# ProDoc_ChisFlash-MBC5-MAX-v1_22-R0603_32.net
KiCad netlist of a schematic drawn in EasyEDA Pro
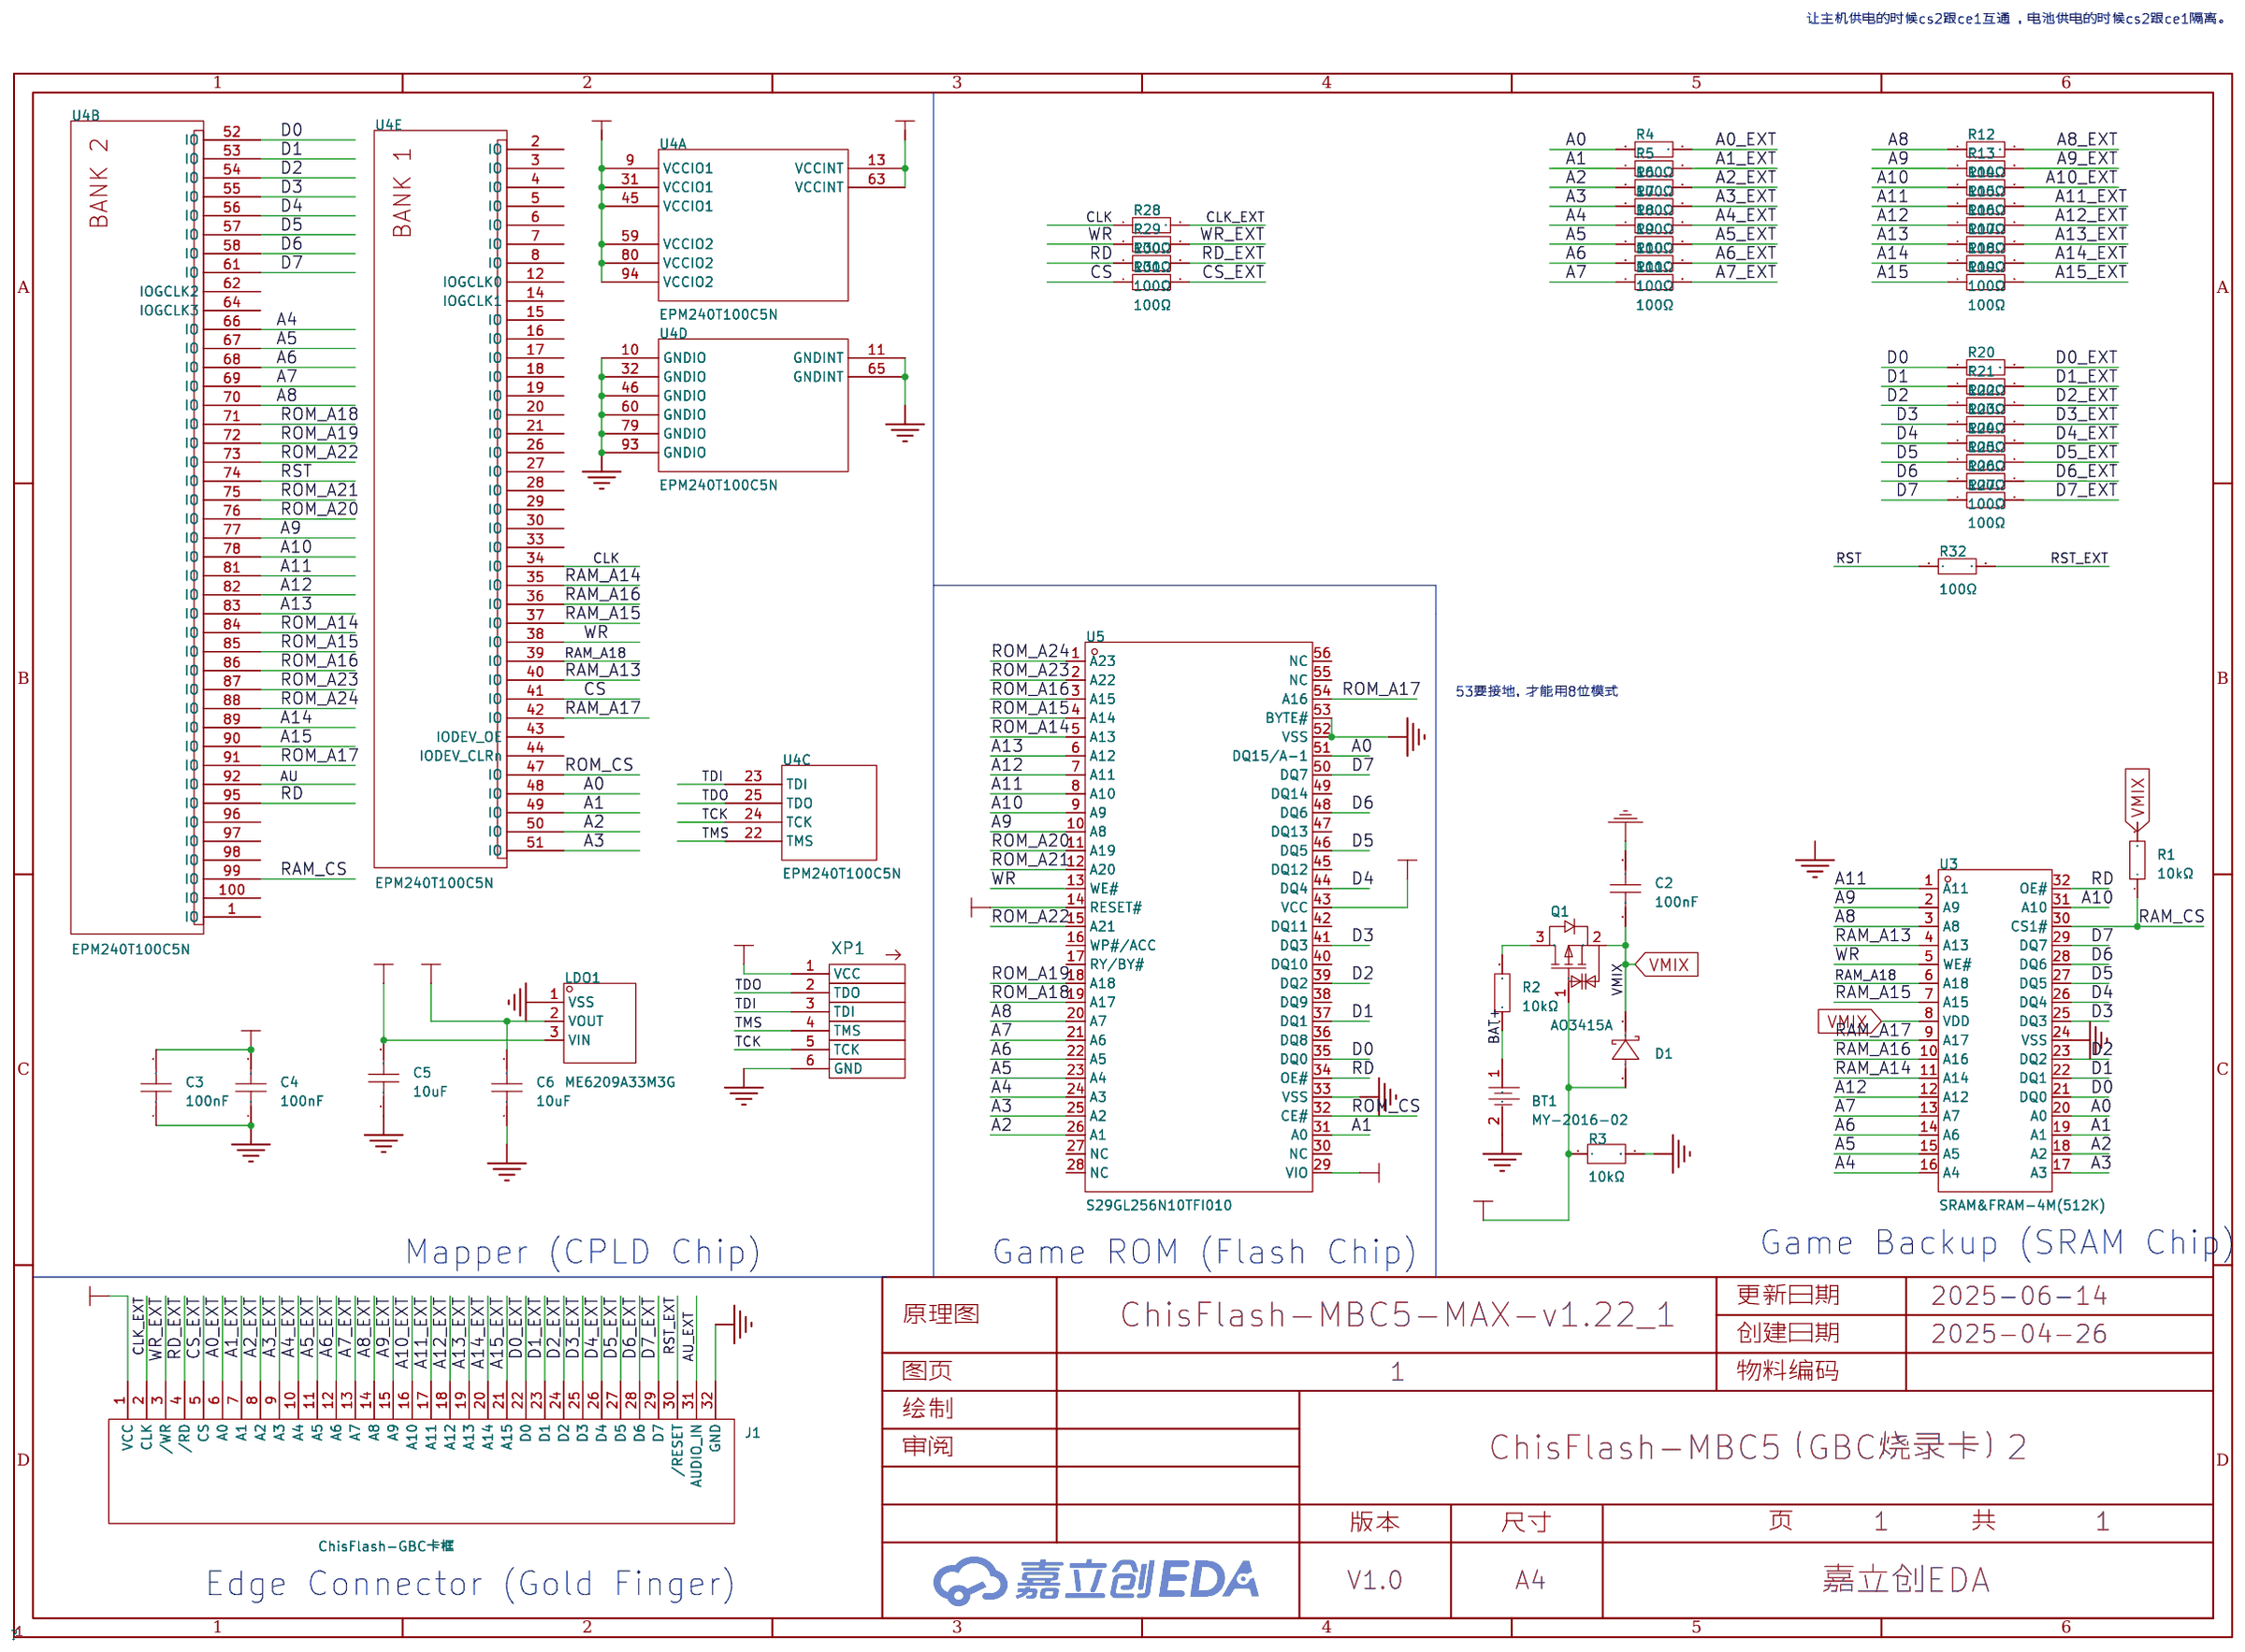
[diagram p0: schematic sheet]

(export (version "E")
  (design (tool "Eeschema 10.0.6"))
  (components
    (comp (ref "BT1")
      (value "MY-2016-02")
      (footprint "easyedapro:BAT-SMD_MY-2032-08")
      (description "连接器类型:电池扣;适用电池规格:CR2016;触头材质:磷青铜;触点电镀:镍;工作温度范围:-25°C~+85°C;")
      (fields (field (name "Manufacturer") "MYOUNG(美阳)"))
      (libsource (lib "easyedapro") (part "MY-2016-02"))
    )
    (comp (ref "C2")
      (value "100nF")
      (footprint "easyedapro:C0603")
      (description "容值:100nF;精度:±10%;额定电压:50V;材质(温度系数):X7R;")
      (fields
        (field (name "Manufacturer Part") "CGA0603X7R104K500JT")
        (field (name "Manufacturer") "HRE(芯声)")
      )
      (libsource (lib "easyedapro") (part "CGA0603X7R104K500JT"))
    )
    (comp (ref "C3")
      (value "100nF")
      (footprint "easyedapro:C0603")
      (description "容值:100nF;精度:±10%;额定电压:50V;材质(温度系数):X7R;")
      (fields
        (field (name "Manufacturer Part") "CGA0603X7R104K500JT")
        (field (name "Manufacturer") "HRE(芯声)")
      )
      (libsource (lib "easyedapro") (part "CGA0603X7R104K500JT"))
    )
    (comp (ref "C4")
      (value "100nF")
      (footprint "easyedapro:C0603")
      (description "容值:100nF;精度:±10%;额定电压:50V;材质(温度系数):X7R;")
      (fields
        (field (name "Manufacturer Part") "CGA0603X7R104K500JT")
        (field (name "Manufacturer") "HRE(芯声)")
      )
      (libsource (lib "easyedapro") (part "CGA0603X7R104K500JT"))
    )
    (comp (ref "C5")
      (value "10uF")
      (footprint "easyedapro:C0603")
      (description "容值:10uF;精度:±20%;额定电压:25V;材质(温度系数):X5R;")
      (fields
        (field (name "Manufacturer Part") "CL10A106MA8NRNC")
        (field (name "Manufacturer") "SAMSUNG(三星)")
      )
      (libsource (lib "easyedapro") (part "CL10A106MA8NRNC"))
    )
    (comp (ref "C6")
      (value "10uF")
      (footprint "easyedapro:C0603")
      (description "容值:10uF;精度:±20%;额定电压:25V;材质(温度系数):X5R;")
      (fields
        (field (name "Manufacturer Part") "CL10A106MA8NRNC")
        (field (name "Manufacturer") "SAMSUNG(三星)")
      )
      (libsource (lib "easyedapro") (part "CL10A106MA8NRNC"))
    )
    (comp (ref "D1")
      (value "RB751V-40")
      (footprint "easyedapro:SOD-323_L1.7-W1.3-LS2.6-RD-1")
      (description "二极管配置:独立式;正向压降(Vf):370mV@1mA;直流反向耐压(Vr):40V;平均整流电流(Io):30mA;")
      (fields (field (name "Manufacturer") "宏迦橙"))
      (libsource (lib "easyedapro") (part "RB751V-40_C7502691"))
    )
    (comp (ref "J1")
      (value "ChisFlash-GBC卡框")
      (footprint "easyedapro:ChisFlash-GBC卡框")
      (libsource (lib "easyedapro") (part "ChisFlash-GBC卡框"))
    )
    (comp (ref "LDO1")
      (value "ME6209A33M3G")
      (footprint "easyedapro:SOT-23-3_L2.9-W1.6-P1.90-LS2.8-BR")
      (description "输出类型:固定;最大输入电压:18V;输出电压:3.3V;最大输出电流:250mA;电源纹波抑制比(PSRR):-;输出极性:正极;")
      (fields (field (name "Manufacturer") "MICRONE(南京微盟)"))
      (libsource (lib "easyedapro") (part "ME6209A33M3G"))
    )
    (comp (ref "Q1")
      (value "AO3415A")
      (footprint "easyedapro:SOT-23-3_L3.0-W1.7-P0.95-LS2.9-BR")
      (fields (field (name "Manufacturer") "UMW(友台半导体)"))
      (libsource (lib "easyedapro") (part "AO3415A_C347479"))
    )
    (comp (ref "R1")
      (value "10kΩ")
      (footprint "easyedapro:R0603")
      (description "电阻类型:厚膜电阻;阻值:10kΩ;精度:±1%;功率:100mW;温度系数:±100ppm/°C;最大工作电压:75V;工作温度范围:-55°C~+155°C;")
      (fields
        (field (name "Manufacturer Part") "0603WAF1002T5E")
        (field (name "Manufacturer") "UNI-ROYAL(厚声)")
      )
      (libsource (lib "easyedapro") (part "0603WAF1002T5E"))
    )
    (comp (ref "R2")
      (value "10kΩ")
      (footprint "easyedapro:R0603")
      (description "电阻类型:厚膜电阻;阻值:10kΩ;精度:±1%;功率:100mW;温度系数:±100ppm/°C;最大工作电压:75V;工作温度范围:-55°C~+155°C;")
      (fields
        (field (name "Manufacturer Part") "0603WAF1002T5E")
        (field (name "Manufacturer") "UNI-ROYAL(厚声)")
      )
      (libsource (lib "easyedapro") (part "0603WAF1002T5E"))
    )
    (comp (ref "R3")
      (value "10kΩ")
      (footprint "easyedapro:R0603")
      (description "电阻类型:薄膜电阻;阻值:10kΩ;精度:±0.1%;功率:100mW;最大工作电压:75V;温度系数:±25ppm/°C;")
      (fields (field (name "Manufacturer Part") "RT0603BRD1010KL") (field (name "Manufacturer") "YAGEO(国巨)"))
      (libsource (lib "easyedapro") (part "RT0603BRD1010KL"))
    )
    (comp (ref "R4")
      (value "100Ω")
      (fields
        (field (name "Manufacturer Part") "0105WHJ0101TDE")
        (field (name "Manufacturer") "UNI-ROYAL(厚声)")
      )
      (libsource (lib "easyedapro") (part "0603WAF1000T5E"))
    )
    (comp (ref "R5")
      (value "100Ω")
      (fields
        (field (name "Manufacturer Part") "0105WHJ0101TDE")
        (field (name "Manufacturer") "UNI-ROYAL(厚声)")
      )
      (libsource (lib "easyedapro") (part "0603WAF1000T5E"))
    )
    (comp (ref "R6")
      (value "100Ω")
      (fields
        (field (name "Manufacturer Part") "0105WHJ0101TDE")
        (field (name "Manufacturer") "UNI-ROYAL(厚声)")
      )
      (libsource (lib "easyedapro") (part "0603WAF1000T5E"))
    )
    (comp (ref "R7")
      (value "100Ω")
      (fields
        (field (name "Manufacturer Part") "0105WHJ0101TDE")
        (field (name "Manufacturer") "UNI-ROYAL(厚声)")
      )
      (libsource (lib "easyedapro") (part "0603WAF1000T5E"))
    )
    (comp (ref "R8")
      (value "100Ω")
      (fields
        (field (name "Manufacturer Part") "0105WHJ0101TDE")
        (field (name "Manufacturer") "UNI-ROYAL(厚声)")
      )
      (libsource (lib "easyedapro") (part "0603WAF1000T5E"))
    )
    (comp (ref "R9")
      (value "100Ω")
      (fields
        (field (name "Manufacturer Part") "0105WHJ0101TDE")
        (field (name "Manufacturer") "UNI-ROYAL(厚声)")
      )
      (libsource (lib "easyedapro") (part "0603WAF1000T5E"))
    )
    (comp (ref "R10")
      (value "100Ω")
      (fields
        (field (name "Manufacturer Part") "0105WHJ0101TDE")
        (field (name "Manufacturer") "UNI-ROYAL(厚声)")
      )
      (libsource (lib "easyedapro") (part "0603WAF1000T5E"))
    )
    (comp (ref "R11")
      (value "100Ω")
      (fields
        (field (name "Manufacturer Part") "0105WHJ0101TDE")
        (field (name "Manufacturer") "UNI-ROYAL(厚声)")
      )
      (libsource (lib "easyedapro") (part "0603WAF1000T5E"))
    )
    (comp (ref "R12")
      (value "100Ω")
      (fields
        (field (name "Manufacturer Part") "0105WHJ0101TDE")
        (field (name "Manufacturer") "UNI-ROYAL(厚声)")
      )
      (libsource (lib "easyedapro") (part "0603WAF1000T5E"))
    )
    (comp (ref "R13")
      (value "100Ω")
      (fields
        (field (name "Manufacturer Part") "0105WHJ0101TDE")
        (field (name "Manufacturer") "UNI-ROYAL(厚声)")
      )
      (libsource (lib "easyedapro") (part "0603WAF1000T5E"))
    )
    (comp (ref "R14")
      (value "100Ω")
      (fields
        (field (name "Manufacturer Part") "0105WHJ0101TDE")
        (field (name "Manufacturer") "UNI-ROYAL(厚声)")
      )
      (libsource (lib "easyedapro") (part "0603WAF1000T5E"))
    )
    (comp (ref "R15")
      (value "100Ω")
      (fields
        (field (name "Manufacturer Part") "0105WHJ0101TDE")
        (field (name "Manufacturer") "UNI-ROYAL(厚声)")
      )
      (libsource (lib "easyedapro") (part "0603WAF1000T5E"))
    )
    (comp (ref "R16")
      (value "100Ω")
      (fields
        (field (name "Manufacturer Part") "0105WHJ0101TDE")
        (field (name "Manufacturer") "UNI-ROYAL(厚声)")
      )
      (libsource (lib "easyedapro") (part "0603WAF1000T5E"))
    )
    (comp (ref "R17")
      (value "100Ω")
      (fields
        (field (name "Manufacturer Part") "0105WHJ0101TDE")
        (field (name "Manufacturer") "UNI-ROYAL(厚声)")
      )
      (libsource (lib "easyedapro") (part "0603WAF1000T5E"))
    )
    (comp (ref "R18")
      (value "100Ω")
      (fields
        (field (name "Manufacturer Part") "0105WHJ0101TDE")
        (field (name "Manufacturer") "UNI-ROYAL(厚声)")
      )
      (libsource (lib "easyedapro") (part "0603WAF1000T5E"))
    )
    (comp (ref "R19")
      (value "100Ω")
      (fields
        (field (name "Manufacturer Part") "0105WHJ0101TDE")
        (field (name "Manufacturer") "UNI-ROYAL(厚声)")
      )
      (libsource (lib "easyedapro") (part "0603WAF1000T5E"))
    )
    (comp (ref "R20")
      (value "100Ω")
      (fields
        (field (name "Manufacturer Part") "0105WHJ0101TDE")
        (field (name "Manufacturer") "UNI-ROYAL(厚声)")
      )
      (libsource (lib "easyedapro") (part "0603WAF1000T5E"))
    )
    (comp (ref "R21")
      (value "100Ω")
      (fields
        (field (name "Manufacturer Part") "0105WHJ0101TDE")
        (field (name "Manufacturer") "UNI-ROYAL(厚声)")
      )
      (libsource (lib "easyedapro") (part "0603WAF1000T5E"))
    )
    (comp (ref "R22")
      (value "100Ω")
      (fields
        (field (name "Manufacturer Part") "0105WHJ0101TDE")
        (field (name "Manufacturer") "UNI-ROYAL(厚声)")
      )
      (libsource (lib "easyedapro") (part "0603WAF1000T5E"))
    )
    (comp (ref "R23")
      (value "100Ω")
      (fields
        (field (name "Manufacturer Part") "0105WHJ0101TDE")
        (field (name "Manufacturer") "UNI-ROYAL(厚声)")
      )
      (libsource (lib "easyedapro") (part "0603WAF1000T5E"))
    )
    (comp (ref "R24")
      (value "100Ω")
      (fields
        (field (name "Manufacturer Part") "0105WHJ0101TDE")
        (field (name "Manufacturer") "UNI-ROYAL(厚声)")
      )
      (libsource (lib "easyedapro") (part "0603WAF1000T5E"))
    )
    (comp (ref "R25")
      (value "100Ω")
      (fields
        (field (name "Manufacturer Part") "0105WHJ0101TDE")
        (field (name "Manufacturer") "UNI-ROYAL(厚声)")
      )
      (libsource (lib "easyedapro") (part "0603WAF1000T5E"))
    )
    (comp (ref "R26")
      (value "100Ω")
      (fields
        (field (name "Manufacturer Part") "0105WHJ0101TDE")
        (field (name "Manufacturer") "UNI-ROYAL(厚声)")
      )
      (libsource (lib "easyedapro") (part "0603WAF1000T5E"))
    )
    (comp (ref "R27")
      (value "100Ω")
      (fields
        (field (name "Manufacturer Part") "0105WHJ0101TDE")
        (field (name "Manufacturer") "UNI-ROYAL(厚声)")
      )
      (libsource (lib "easyedapro") (part "0603WAF1000T5E"))
    )
    (comp (ref "R28")
      (value "100Ω")
      (fields
        (field (name "Manufacturer Part") "0105WHJ0101TDE")
        (field (name "Manufacturer") "UNI-ROYAL(厚声)")
      )
      (libsource (lib "easyedapro") (part "0603WAF1000T5E"))
    )
    (comp (ref "R29")
      (value "100Ω")
      (fields
        (field (name "Manufacturer Part") "0105WHJ0101TDE")
        (field (name "Manufacturer") "UNI-ROYAL(厚声)")
      )
      (libsource (lib "easyedapro") (part "0603WAF1000T5E"))
    )
    (comp (ref "R30")
      (value "100Ω")
      (fields
        (field (name "Manufacturer Part") "0105WHJ0101TDE")
        (field (name "Manufacturer") "UNI-ROYAL(厚声)")
      )
      (libsource (lib "easyedapro") (part "0603WAF1000T5E"))
    )
    (comp (ref "R31")
      (value "100Ω")
      (fields
        (field (name "Manufacturer Part") "0105WHJ0101TDE")
        (field (name "Manufacturer") "UNI-ROYAL(厚声)")
      )
      (libsource (lib "easyedapro") (part "0603WAF1000T5E"))
    )
    (comp (ref "R32")
      (value "100Ω")
      (fields
        (field (name "Manufacturer Part") "0105WHJ0101TDE")
        (field (name "Manufacturer") "UNI-ROYAL(厚声)")
      )
      (libsource (lib "easyedapro") (part "0603WAF1000T5E"))
    )
    (comp (ref "U3")
      (value "SRAM&FRAM-4M(512K)")
      (footprint "easyedapro:TSSOP-TSOP二合一_1")
      (libsource (lib "easyedapro") (part "SRAM&FRAM-4M(512K)"))
    )
    (comp (ref "U4")
      (value "EPM240T100C5N")
      (footprint "easyedapro:TQFP-100_L14.0-W14.0-P0.50-LS16.0-BL")
      (description "类型:其它PLD;逻辑门数量:-;逻辑单元数:-;逻辑阵列块数:240;")
      (fields (field (name "Manufacturer") "Intel/Altera"))
      (libsource (lib "easyedapro") (part "EPM240T100C5N"))
    )
    (comp (ref "U5")
      (value "S29GL256N10TFI010")
      (footprint "easyedapro:TSOP-56_L18.4-W14.0-P0.50-LS20.0-TL")
      (libsource (lib "easyedapro") (part "S29GL256N10TFI010"))
    )
    (comp (ref "XP1")
      (value "JTAG")
      (footprint "easyedapro:HDR-TH_6P-P1.27-V-M-1")
      (libsource (lib "easyedapro") (part "jtag"))
    )
  )
  (nets
    (net (code "1") (name "+3V3") (class "Default")
      (node (ref "C3") (pin "2") (pinfunction "2_2") (pintype "unspecified"))
      (node (ref "C4") (pin "2") (pinfunction "2_2") (pintype "unspecified"))
      (node (ref "C6") (pin "2") (pinfunction "2_2") (pintype "unspecified"))
      (node (ref "D1") (pin "2") (pinfunction "A_2") (pintype "unspecified"))
      (node (ref "LDO1") (pin "2") (pinfunction "VOUT_2") (pintype "unspecified"))
      (node (ref "Q1") (pin "1") (pinfunction "G_1") (pintype "unspecified"))
      (node (ref "R3") (pin "1") (pinfunction "1_1") (pintype "unspecified"))
      (node (ref "U4") (pin "13") (pinfunction "VCCINT_13") (pintype "unspecified"))
      (node (ref "U4") (pin "31") (pinfunction "VCCIO1_31") (pintype "unspecified"))
      (node (ref "U4") (pin "45") (pinfunction "VCCIO1_45") (pintype "unspecified"))
      (node (ref "U4") (pin "59") (pinfunction "VCCIO2_59") (pintype "unspecified"))
      (node (ref "U4") (pin "63") (pinfunction "VCCINT_63") (pintype "unspecified"))
      (node (ref "U4") (pin "80") (pinfunction "VCCIO2_80") (pintype "unspecified"))
      (node (ref "U4") (pin "9") (pinfunction "VCCIO1_9") (pintype "unspecified"))
      (node (ref "U4") (pin "94") (pinfunction "VCCIO2_94") (pintype "unspecified"))
      (node (ref "U5") (pin "14") (pinfunction "RESET#_14") (pintype "unspecified"))
      (node (ref "U5") (pin "29") (pinfunction "VIO_29") (pintype "unspecified"))
      (node (ref "U5") (pin "43") (pinfunction "VCC_43") (pintype "unspecified"))
      (node (ref "XP1") (pin "1") (pinfunction "VCC_1") (pintype "output"))
    )
    (net (code "2") (name "+5V") (class "Default")
      (node (ref "C5") (pin "2") (pinfunction "2_2") (pintype "unspecified"))
      (node (ref "J1") (pin "1") (pinfunction "VCC_1") (pintype "unspecified"))
      (node (ref "LDO1") (pin "3") (pinfunction "VIN_3") (pintype "unspecified"))
    )
    (net (code "3") (name "/A0") (class "Default")
      (node (ref "R4") (pin "1") (pinfunction "1_1") (pintype "input"))
      (node (ref "U3") (pin "20") (pinfunction "A0_20") (pintype "unspecified"))
      (node (ref "U4") (pin "48") (pinfunction "IO_48") (pintype "bidirectional"))
      (node (ref "U5") (pin "51") (pinfunction "DQ15/A-1_51") (pintype "unspecified"))
    )
    (net (code "4") (name "/A0_EXT") (class "Default")
      (node (ref "J1") (pin "6") (pinfunction "A0_6") (pintype "unspecified"))
      (node (ref "R4") (pin "2") (pinfunction "2_2") (pintype "input"))
    )
    (net (code "5") (name "/A1") (class "Default")
      (node (ref "R5") (pin "1") (pinfunction "1_1") (pintype "input"))
      (node (ref "U3") (pin "19") (pinfunction "A1_19") (pintype "unspecified"))
      (node (ref "U4") (pin "49") (pinfunction "IO_49") (pintype "bidirectional"))
      (node (ref "U5") (pin "31") (pinfunction "A0_31") (pintype "unspecified"))
    )
    (net (code "6") (name "/A1_EXT") (class "Default")
      (node (ref "J1") (pin "7") (pinfunction "A1_7") (pintype "unspecified"))
      (node (ref "R5") (pin "2") (pinfunction "2_2") (pintype "input"))
    )
    (net (code "7") (name "/A2") (class "Default")
      (node (ref "R6") (pin "1") (pinfunction "1_1") (pintype "input"))
      (node (ref "U3") (pin "18") (pinfunction "A2_18") (pintype "unspecified"))
      (node (ref "U4") (pin "50") (pinfunction "IO_50") (pintype "bidirectional"))
      (node (ref "U5") (pin "26") (pinfunction "A1_26") (pintype "unspecified"))
    )
    (net (code "8") (name "/A2_EXT") (class "Default")
      (node (ref "J1") (pin "8") (pinfunction "A2_8") (pintype "unspecified"))
      (node (ref "R6") (pin "2") (pinfunction "2_2") (pintype "input"))
    )
    (net (code "9") (name "/A3") (class "Default")
      (node (ref "R7") (pin "1") (pinfunction "1_1") (pintype "input"))
      (node (ref "U3") (pin "17") (pinfunction "A3_17") (pintype "unspecified"))
      (node (ref "U4") (pin "51") (pinfunction "IO_51") (pintype "bidirectional"))
      (node (ref "U5") (pin "25") (pinfunction "A2_25") (pintype "unspecified"))
    )
    (net (code "10") (name "/A3_EXT") (class "Default")
      (node (ref "J1") (pin "9") (pinfunction "A3_9") (pintype "unspecified"))
      (node (ref "R7") (pin "2") (pinfunction "2_2") (pintype "input"))
    )
    (net (code "11") (name "/A4") (class "Default")
      (node (ref "R8") (pin "1") (pinfunction "1_1") (pintype "input"))
      (node (ref "U3") (pin "16") (pinfunction "A4_16") (pintype "unspecified"))
      (node (ref "U4") (pin "66") (pinfunction "IO_66") (pintype "bidirectional"))
      (node (ref "U5") (pin "24") (pinfunction "A3_24") (pintype "unspecified"))
    )
    (net (code "12") (name "/A4_EXT") (class "Default")
      (node (ref "J1") (pin "10") (pinfunction "A4_10") (pintype "unspecified"))
      (node (ref "R8") (pin "2") (pinfunction "2_2") (pintype "input"))
    )
    (net (code "13") (name "/A5") (class "Default")
      (node (ref "R9") (pin "1") (pinfunction "1_1") (pintype "input"))
      (node (ref "U3") (pin "15") (pinfunction "A5_15") (pintype "unspecified"))
      (node (ref "U4") (pin "67") (pinfunction "IO_67") (pintype "bidirectional"))
      (node (ref "U5") (pin "23") (pinfunction "A4_23") (pintype "unspecified"))
    )
    (net (code "14") (name "/A5_EXT") (class "Default")
      (node (ref "J1") (pin "11") (pinfunction "A5_11") (pintype "unspecified"))
      (node (ref "R9") (pin "2") (pinfunction "2_2") (pintype "input"))
    )
    (net (code "15") (name "/A6") (class "Default")
      (node (ref "R10") (pin "1") (pinfunction "1_1") (pintype "input"))
      (node (ref "U3") (pin "14") (pinfunction "A6_14") (pintype "unspecified"))
      (node (ref "U4") (pin "68") (pinfunction "IO_68") (pintype "bidirectional"))
      (node (ref "U5") (pin "22") (pinfunction "A5_22") (pintype "unspecified"))
    )
    (net (code "16") (name "/A6_EXT") (class "Default")
      (node (ref "J1") (pin "12") (pinfunction "A6_12") (pintype "unspecified"))
      (node (ref "R10") (pin "2") (pinfunction "2_2") (pintype "input"))
    )
    (net (code "17") (name "/A7") (class "Default")
      (node (ref "R11") (pin "1") (pinfunction "1_1") (pintype "input"))
      (node (ref "U3") (pin "13") (pinfunction "A7_13") (pintype "unspecified"))
      (node (ref "U4") (pin "69") (pinfunction "IO_69") (pintype "bidirectional"))
      (node (ref "U5") (pin "21") (pinfunction "A6_21") (pintype "unspecified"))
    )
    (net (code "18") (name "/A7_EXT") (class "Default")
      (node (ref "J1") (pin "13") (pinfunction "A7_13") (pintype "unspecified"))
      (node (ref "R11") (pin "2") (pinfunction "2_2") (pintype "input"))
    )
    (net (code "19") (name "/A8") (class "Default")
      (node (ref "R12") (pin "1") (pinfunction "1_1") (pintype "input"))
      (node (ref "U3") (pin "3") (pinfunction "A8_3") (pintype "unspecified"))
      (node (ref "U4") (pin "70") (pinfunction "IO_70") (pintype "bidirectional"))
      (node (ref "U5") (pin "20") (pinfunction "A7_20") (pintype "unspecified"))
    )
    (net (code "20") (name "/A8_EXT") (class "Default")
      (node (ref "J1") (pin "14") (pinfunction "A8_14") (pintype "unspecified"))
      (node (ref "R12") (pin "2") (pinfunction "2_2") (pintype "input"))
    )
    (net (code "21") (name "/A9") (class "Default")
      (node (ref "R13") (pin "1") (pinfunction "1_1") (pintype "input"))
      (node (ref "U3") (pin "2") (pinfunction "A9_2") (pintype "unspecified"))
      (node (ref "U4") (pin "77") (pinfunction "IO_77") (pintype "bidirectional"))
      (node (ref "U5") (pin "10") (pinfunction "A8_10") (pintype "unspecified"))
    )
    (net (code "22") (name "/A9_EXT") (class "Default")
      (node (ref "J1") (pin "15") (pinfunction "A9_15") (pintype "unspecified"))
      (node (ref "R13") (pin "2") (pinfunction "2_2") (pintype "input"))
    )
    (net (code "23") (name "/A10") (class "Default")
      (node (ref "R14") (pin "1") (pinfunction "1_1") (pintype "input"))
      (node (ref "U3") (pin "31") (pinfunction "A10_31") (pintype "unspecified"))
      (node (ref "U4") (pin "78") (pinfunction "IO_78") (pintype "bidirectional"))
      (node (ref "U5") (pin "9") (pinfunction "A9_9") (pintype "unspecified"))
    )
    (net (code "24") (name "/A10_EXT") (class "Default")
      (node (ref "J1") (pin "16") (pinfunction "A10_16") (pintype "unspecified"))
      (node (ref "R14") (pin "2") (pinfunction "2_2") (pintype "input"))
    )
    (net (code "25") (name "/A11") (class "Default")
      (node (ref "R15") (pin "1") (pinfunction "1_1") (pintype "input"))
      (node (ref "U3") (pin "1") (pinfunction "A11_1") (pintype "unspecified"))
      (node (ref "U4") (pin "81") (pinfunction "IO_81") (pintype "bidirectional"))
      (node (ref "U5") (pin "8") (pinfunction "A10_8") (pintype "unspecified"))
    )
    (net (code "26") (name "/A11_EXT") (class "Default")
      (node (ref "J1") (pin "17") (pinfunction "A11_17") (pintype "unspecified"))
      (node (ref "R15") (pin "2") (pinfunction "2_2") (pintype "input"))
    )
    (net (code "27") (name "/A12") (class "Default")
      (node (ref "R16") (pin "1") (pinfunction "1_1") (pintype "input"))
      (node (ref "U3") (pin "12") (pinfunction "A12_12") (pintype "unspecified"))
      (node (ref "U4") (pin "82") (pinfunction "IO_82") (pintype "bidirectional"))
      (node (ref "U5") (pin "7") (pinfunction "A11_7") (pintype "unspecified"))
    )
    (net (code "28") (name "/A12_EXT") (class "Default")
      (node (ref "J1") (pin "18") (pinfunction "A12_18") (pintype "unspecified"))
      (node (ref "R16") (pin "2") (pinfunction "2_2") (pintype "input"))
    )
    (net (code "29") (name "/A13") (class "Default")
      (node (ref "R17") (pin "1") (pinfunction "1_1") (pintype "input"))
      (node (ref "U4") (pin "83") (pinfunction "IO_83") (pintype "bidirectional"))
      (node (ref "U5") (pin "6") (pinfunction "A12_6") (pintype "unspecified"))
    )
    (net (code "30") (name "/A13_EXT") (class "Default")
      (node (ref "J1") (pin "19") (pinfunction "A13_19") (pintype "unspecified"))
      (node (ref "R17") (pin "2") (pinfunction "2_2") (pintype "input"))
    )
    (net (code "31") (name "/A14") (class "Default")
      (node (ref "R18") (pin "1") (pinfunction "1_1") (pintype "input"))
      (node (ref "U4") (pin "89") (pinfunction "IO_89") (pintype "bidirectional"))
    )
    (net (code "32") (name "/A14_EXT") (class "Default")
      (node (ref "J1") (pin "20") (pinfunction "A14_20") (pintype "unspecified"))
      (node (ref "R18") (pin "2") (pinfunction "2_2") (pintype "input"))
    )
    (net (code "33") (name "/A15") (class "Default")
      (node (ref "R19") (pin "1") (pinfunction "1_1") (pintype "input"))
      (node (ref "U4") (pin "90") (pinfunction "IO_90") (pintype "bidirectional"))
    )
    (net (code "34") (name "/A15_EXT") (class "Default")
      (node (ref "J1") (pin "21") (pinfunction "A15_21") (pintype "unspecified"))
      (node (ref "R19") (pin "2") (pinfunction "2_2") (pintype "input"))
    )
    (net (code "35") (name "/AU") (class "Default")
      (node (ref "U4") (pin "92") (pinfunction "IO_92") (pintype "bidirectional"))
    )
    (net (code "36") (name "/AU_EXT") (class "Default")
      (node (ref "J1") (pin "31") (pinfunction "AUDIO_IN_31") (pintype "unspecified"))
    )
    (net (code "37") (name "/BAT+") (class "Default")
      (node (ref "BT1") (pin "1") (pinfunction "1_1") (pintype "input"))
      (node (ref "R2") (pin "1") (pinfunction "1_1") (pintype "input"))
    )
    (net (code "38") (name "/CLK") (class "Default")
      (node (ref "R28") (pin "1") (pinfunction "1_1") (pintype "input"))
      (node (ref "U4") (pin "34") (pinfunction "IO_34") (pintype "bidirectional"))
    )
    (net (code "39") (name "/CLK_EXT") (class "Default")
      (node (ref "J1") (pin "2") (pinfunction "CLK_2") (pintype "unspecified"))
      (node (ref "R28") (pin "2") (pinfunction "2_2") (pintype "input"))
    )
    (net (code "40") (name "/CS") (class "Default")
      (node (ref "R31") (pin "1") (pinfunction "1_1") (pintype "input"))
      (node (ref "U4") (pin "41") (pinfunction "IO_41") (pintype "bidirectional"))
    )
    (net (code "41") (name "/CS_EXT") (class "Default")
      (node (ref "J1") (pin "5") (pinfunction "CS_5") (pintype "unspecified"))
      (node (ref "R31") (pin "2") (pinfunction "2_2") (pintype "input"))
    )
    (net (code "42") (name "/D0") (class "Default")
      (node (ref "R20") (pin "1") (pinfunction "1_1") (pintype "input"))
      (node (ref "U3") (pin "21") (pinfunction "DQ0_21") (pintype "unspecified"))
      (node (ref "U4") (pin "52") (pinfunction "IO_52") (pintype "bidirectional"))
      (node (ref "U5") (pin "35") (pinfunction "DQ0_35") (pintype "unspecified"))
    )
    (net (code "43") (name "/D0_EXT") (class "Default")
      (node (ref "J1") (pin "22") (pinfunction "D0_22") (pintype "unspecified"))
      (node (ref "R20") (pin "2") (pinfunction "2_2") (pintype "input"))
    )
    (net (code "44") (name "/D1") (class "Default")
      (node (ref "R21") (pin "1") (pinfunction "1_1") (pintype "input"))
      (node (ref "U3") (pin "22") (pinfunction "DQ1_22") (pintype "unspecified"))
      (node (ref "U4") (pin "53") (pinfunction "IO_53") (pintype "bidirectional"))
      (node (ref "U5") (pin "37") (pinfunction "DQ1_37") (pintype "unspecified"))
    )
    (net (code "45") (name "/D1_EXT") (class "Default")
      (node (ref "J1") (pin "23") (pinfunction "D1_23") (pintype "unspecified"))
      (node (ref "R21") (pin "2") (pinfunction "2_2") (pintype "input"))
    )
    (net (code "46") (name "/D2") (class "Default")
      (node (ref "R22") (pin "1") (pinfunction "1_1") (pintype "input"))
      (node (ref "U3") (pin "23") (pinfunction "DQ2_23") (pintype "unspecified"))
      (node (ref "U4") (pin "54") (pinfunction "IO_54") (pintype "bidirectional"))
      (node (ref "U5") (pin "39") (pinfunction "DQ2_39") (pintype "unspecified"))
    )
    (net (code "47") (name "/D2_EXT") (class "Default")
      (node (ref "J1") (pin "24") (pinfunction "D2_24") (pintype "unspecified"))
      (node (ref "R22") (pin "2") (pinfunction "2_2") (pintype "input"))
    )
    (net (code "48") (name "/D3") (class "Default")
      (node (ref "R23") (pin "1") (pinfunction "1_1") (pintype "input"))
      (node (ref "U3") (pin "25") (pinfunction "DQ3_25") (pintype "unspecified"))
      (node (ref "U4") (pin "55") (pinfunction "IO_55") (pintype "bidirectional"))
      (node (ref "U5") (pin "41") (pinfunction "DQ3_41") (pintype "unspecified"))
    )
    (net (code "49") (name "/D3_EXT") (class "Default")
      (node (ref "J1") (pin "25") (pinfunction "D3_25") (pintype "unspecified"))
      (node (ref "R23") (pin "2") (pinfunction "2_2") (pintype "input"))
    )
    (net (code "50") (name "/D4") (class "Default")
      (node (ref "R24") (pin "1") (pinfunction "1_1") (pintype "input"))
      (node (ref "U3") (pin "26") (pinfunction "DQ4_26") (pintype "unspecified"))
      (node (ref "U4") (pin "56") (pinfunction "IO_56") (pintype "bidirectional"))
      (node (ref "U5") (pin "44") (pinfunction "DQ4_44") (pintype "unspecified"))
    )
    (net (code "51") (name "/D4_EXT") (class "Default")
      (node (ref "J1") (pin "26") (pinfunction "D4_26") (pintype "unspecified"))
      (node (ref "R24") (pin "2") (pinfunction "2_2") (pintype "input"))
    )
    (net (code "52") (name "/D5") (class "Default")
      (node (ref "R25") (pin "1") (pinfunction "1_1") (pintype "input"))
      (node (ref "U3") (pin "27") (pinfunction "DQ5_27") (pintype "unspecified"))
      (node (ref "U4") (pin "57") (pinfunction "IO_57") (pintype "bidirectional"))
      (node (ref "U5") (pin "46") (pinfunction "DQ5_46") (pintype "unspecified"))
    )
    (net (code "53") (name "/D5_EXT") (class "Default")
      (node (ref "J1") (pin "27") (pinfunction "D5_27") (pintype "unspecified"))
      (node (ref "R25") (pin "2") (pinfunction "2_2") (pintype "input"))
    )
    (net (code "54") (name "/D6") (class "Default")
      (node (ref "R26") (pin "1") (pinfunction "1_1") (pintype "input"))
      (node (ref "U3") (pin "28") (pinfunction "DQ6_28") (pintype "unspecified"))
      (node (ref "U4") (pin "58") (pinfunction "IO_58") (pintype "bidirectional"))
      (node (ref "U5") (pin "48") (pinfunction "DQ6_48") (pintype "unspecified"))
    )
    (net (code "55") (name "/D6_EXT") (class "Default")
      (node (ref "J1") (pin "28") (pinfunction "D6_28") (pintype "unspecified"))
      (node (ref "R26") (pin "2") (pinfunction "2_2") (pintype "input"))
    )
    (net (code "56") (name "/D7") (class "Default")
      (node (ref "R27") (pin "1") (pinfunction "1_1") (pintype "input"))
      (node (ref "U3") (pin "29") (pinfunction "DQ7_29") (pintype "unspecified"))
      (node (ref "U4") (pin "61") (pinfunction "IO_61") (pintype "bidirectional"))
      (node (ref "U5") (pin "50") (pinfunction "DQ7_50") (pintype "unspecified"))
    )
    (net (code "57") (name "/D7_EXT") (class "Default")
      (node (ref "J1") (pin "29") (pinfunction "D7_29") (pintype "unspecified"))
      (node (ref "R27") (pin "2") (pinfunction "2_2") (pintype "input"))
    )
    (net (code "58") (name "/RAM_A13") (class "Default")
      (node (ref "U3") (pin "4") (pinfunction "A13_4") (pintype "unspecified"))
      (node (ref "U4") (pin "40") (pinfunction "IO_40") (pintype "bidirectional"))
    )
    (net (code "59") (name "/RAM_A14") (class "Default")
      (node (ref "U3") (pin "11") (pinfunction "A14_11") (pintype "unspecified"))
      (node (ref "U4") (pin "35") (pinfunction "IO_35") (pintype "bidirectional"))
    )
    (net (code "60") (name "/RAM_A15") (class "Default")
      (node (ref "U3") (pin "7") (pinfunction "A15_7") (pintype "unspecified"))
      (node (ref "U4") (pin "37") (pinfunction "IO_37") (pintype "bidirectional"))
    )
    (net (code "61") (name "/RAM_A16") (class "Default")
      (node (ref "U3") (pin "10") (pinfunction "A16_10") (pintype "unspecified"))
      (node (ref "U4") (pin "36") (pinfunction "IO_36") (pintype "bidirectional"))
    )
    (net (code "62") (name "/RAM_A17") (class "Default")
      (node (ref "U3") (pin "9") (pinfunction "A17_9") (pintype "unspecified"))
      (node (ref "U4") (pin "42") (pinfunction "IO_42") (pintype "bidirectional"))
    )
    (net (code "63") (name "/RAM_A18") (class "Default")
      (node (ref "U3") (pin "6") (pinfunction "A18_6") (pintype "unspecified"))
      (node (ref "U4") (pin "39") (pinfunction "IO_39") (pintype "bidirectional"))
    )
    (net (code "64") (name "/RAM_CS") (class "Default")
      (node (ref "R1") (pin "1") (pinfunction "1_1") (pintype "input"))
      (node (ref "U3") (pin "30") (pinfunction "CS1#_30") (pintype "unspecified"))
      (node (ref "U4") (pin "99") (pinfunction "IO_99") (pintype "bidirectional"))
    )
    (net (code "65") (name "/RD") (class "Default")
      (node (ref "R30") (pin "1") (pinfunction "1_1") (pintype "input"))
      (node (ref "U3") (pin "32") (pinfunction "OE#_32") (pintype "unspecified"))
      (node (ref "U4") (pin "95") (pinfunction "IO_95") (pintype "bidirectional"))
      (node (ref "U5") (pin "34") (pinfunction "OE#_34") (pintype "unspecified"))
    )
    (net (code "66") (name "/RD_EXT") (class "Default")
      (node (ref "J1") (pin "4") (pinfunction "/RD_4") (pintype "unspecified"))
      (node (ref "R30") (pin "2") (pinfunction "2_2") (pintype "input"))
    )
    (net (code "67") (name "/ROM_A14") (class "Default")
      (node (ref "U4") (pin "84") (pinfunction "IO_84") (pintype "bidirectional"))
      (node (ref "U5") (pin "5") (pinfunction "A13_5") (pintype "unspecified"))
    )
    (net (code "68") (name "/ROM_A15") (class "Default")
      (node (ref "U4") (pin "85") (pinfunction "IO_85") (pintype "bidirectional"))
      (node (ref "U5") (pin "4") (pinfunction "A14_4") (pintype "unspecified"))
    )
    (net (code "69") (name "/ROM_A16") (class "Default")
      (node (ref "U4") (pin "86") (pinfunction "IO_86") (pintype "bidirectional"))
      (node (ref "U5") (pin "3") (pinfunction "A15_3") (pintype "unspecified"))
    )
    (net (code "70") (name "/ROM_A17") (class "Default")
      (node (ref "U4") (pin "91") (pinfunction "IO_91") (pintype "bidirectional"))
      (node (ref "U5") (pin "54") (pinfunction "A16_54") (pintype "unspecified"))
    )
    (net (code "71") (name "/ROM_A18") (class "Default")
      (node (ref "U4") (pin "71") (pinfunction "IO_71") (pintype "bidirectional"))
      (node (ref "U5") (pin "19") (pinfunction "A17_19") (pintype "unspecified"))
    )
    (net (code "72") (name "/ROM_A19") (class "Default")
      (node (ref "U4") (pin "72") (pinfunction "IO_72") (pintype "bidirectional"))
      (node (ref "U5") (pin "18") (pinfunction "A18_18") (pintype "unspecified"))
    )
    (net (code "73") (name "/ROM_A20") (class "Default")
      (node (ref "U4") (pin "76") (pinfunction "IO_76") (pintype "bidirectional"))
      (node (ref "U5") (pin "11") (pinfunction "A19_11") (pintype "unspecified"))
    )
    (net (code "74") (name "/ROM_A21") (class "Default")
      (node (ref "U4") (pin "75") (pinfunction "IO_75") (pintype "bidirectional"))
      (node (ref "U5") (pin "12") (pinfunction "A20_12") (pintype "unspecified"))
    )
    (net (code "75") (name "/ROM_A22") (class "Default")
      (node (ref "U4") (pin "73") (pinfunction "IO_73") (pintype "bidirectional"))
      (node (ref "U5") (pin "15") (pinfunction "A21_15") (pintype "unspecified"))
    )
    (net (code "76") (name "/ROM_A23") (class "Default")
      (node (ref "U4") (pin "87") (pinfunction "IO_87") (pintype "bidirectional"))
      (node (ref "U5") (pin "2") (pinfunction "A22_2") (pintype "unspecified"))
    )
    (net (code "77") (name "/ROM_A24") (class "Default")
      (node (ref "U4") (pin "88") (pinfunction "IO_88") (pintype "bidirectional"))
      (node (ref "U5") (pin "1") (pinfunction "A23_1") (pintype "unspecified"))
    )
    (net (code "78") (name "/ROM_CS") (class "Default")
      (node (ref "U4") (pin "47") (pinfunction "IO_47") (pintype "bidirectional"))
      (node (ref "U5") (pin "32") (pinfunction "CE#_32") (pintype "unspecified"))
    )
    (net (code "79") (name "/RST") (class "Default")
      (node (ref "R32") (pin "1") (pinfunction "1_1") (pintype "input"))
      (node (ref "U4") (pin "74") (pinfunction "IO_74") (pintype "bidirectional"))
    )
    (net (code "80") (name "/RST_EXT") (class "Default")
      (node (ref "J1") (pin "30") (pinfunction "/RESET_30") (pintype "unspecified"))
      (node (ref "R32") (pin "2") (pinfunction "2_2") (pintype "input"))
    )
    (net (code "81") (name "/TCK") (class "Default")
      (node (ref "U4") (pin "24") (pinfunction "TCK_24") (pintype "unspecified"))
      (node (ref "XP1") (pin "5") (pinfunction "TCK_5") (pintype "input"))
    )
    (net (code "82") (name "/TDI") (class "Default")
      (node (ref "U4") (pin "23") (pinfunction "TDI_23") (pintype "unspecified"))
      (node (ref "XP1") (pin "3") (pinfunction "TDI_3") (pintype "output"))
    )
    (net (code "83") (name "/TDO") (class "Default")
      (node (ref "U4") (pin "25") (pinfunction "TDO_25") (pintype "output"))
      (node (ref "XP1") (pin "2") (pinfunction "TDO_2") (pintype "output"))
    )
    (net (code "84") (name "/TMS") (class "Default")
      (node (ref "U4") (pin "22") (pinfunction "TMS_22") (pintype "unspecified"))
      (node (ref "XP1") (pin "4") (pinfunction "TMS_4") (pintype "output"))
    )
    (net (code "85") (name "/WR") (class "Default")
      (node (ref "R29") (pin "1") (pinfunction "1_1") (pintype "input"))
      (node (ref "U3") (pin "5") (pinfunction "WE#_5") (pintype "unspecified"))
      (node (ref "U4") (pin "38") (pinfunction "IO_38") (pintype "bidirectional"))
      (node (ref "U5") (pin "13") (pinfunction "WE#_13") (pintype "unspecified"))
    )
    (net (code "86") (name "/WR_EXT") (class "Default")
      (node (ref "J1") (pin "3") (pinfunction "/WR_3") (pintype "unspecified"))
      (node (ref "R29") (pin "2") (pinfunction "2_2") (pintype "input"))
    )
    (net (code "87") (name "GND") (class "Default")
      (node (ref "BT1") (pin "2") (pinfunction "2_2") (pintype "input"))
      (node (ref "C2") (pin "1") (pinfunction "1_1") (pintype "unspecified"))
      (node (ref "C3") (pin "1") (pinfunction "1_1") (pintype "unspecified"))
      (node (ref "C4") (pin "1") (pinfunction "1_1") (pintype "unspecified"))
      (node (ref "C5") (pin "1") (pinfunction "1_1") (pintype "unspecified"))
      (node (ref "C6") (pin "1") (pinfunction "1_1") (pintype "unspecified"))
      (node (ref "J1") (pin "32") (pinfunction "GND_32") (pintype "unspecified"))
      (node (ref "LDO1") (pin "1") (pinfunction "VSS_1") (pintype "unspecified"))
      (node (ref "R3") (pin "2") (pinfunction "2_2") (pintype "unspecified"))
      (node (ref "U3") (pin "24") (pinfunction "VSS_24") (pintype "unspecified"))
      (node (ref "U4") (pin "10") (pinfunction "GNDIO_10") (pintype "unspecified"))
      (node (ref "U4") (pin "11") (pinfunction "GNDINT_11") (pintype "unspecified"))
      (node (ref "U4") (pin "32") (pinfunction "GNDIO_32") (pintype "unspecified"))
      (node (ref "U4") (pin "46") (pinfunction "GNDIO_46") (pintype "unspecified"))
      (node (ref "U4") (pin "60") (pinfunction "GNDIO_60") (pintype "unspecified"))
      (node (ref "U4") (pin "65") (pinfunction "GNDINT_65") (pintype "unspecified"))
      (node (ref "U4") (pin "79") (pinfunction "GNDIO_79") (pintype "unspecified"))
      (node (ref "U4") (pin "93") (pinfunction "GNDIO_93") (pintype "unspecified"))
      (node (ref "U5") (pin "33") (pinfunction "VSS_33") (pintype "unspecified"))
      (node (ref "U5") (pin "52") (pinfunction "VSS_52") (pintype "unspecified"))
      (node (ref "U5") (pin "53") (pinfunction "BYTE#_53") (pintype "unspecified"))
      (node (ref "XP1") (pin "6") (pinfunction "GND_6") (pintype "input"))
    )
    (net (code "88") (name "Net-(Q1-D)") (class "Default")
      (node (ref "Q1") (pin "3") (pinfunction "D_3") (pintype "unspecified"))
      (node (ref "R2") (pin "2") (pinfunction "2_2") (pintype "input"))
    )
    (net (code "89") (name "VMIX") (class "Default")
      (node (ref "C2") (pin "2") (pinfunction "2_2") (pintype "unspecified"))
      (node (ref "D1") (pin "1") (pinfunction "K_1") (pintype "unspecified"))
      (node (ref "Q1") (pin "2") (pinfunction "S_2") (pintype "unspecified"))
      (node (ref "R1") (pin "2") (pinfunction "2_2") (pintype "input"))
      (node (ref "U3") (pin "8") (pinfunction "VDD_8") (pintype "unspecified"))
    )
    (net (code "90") (name "unconnected-(U4B-IO-Pad1)") (class "Default")
      (node (ref "U4") (pin "1") (pinfunction "IO_1") (pintype "bidirectional"))
    )
    (net (code "91") (name "unconnected-(U4B-IO-Pad96)") (class "Default")
      (node (ref "U4") (pin "96") (pinfunction "IO_96") (pintype "bidirectional"))
    )
    (net (code "92") (name "unconnected-(U4B-IO-Pad97)") (class "Default")
      (node (ref "U4") (pin "97") (pinfunction "IO_97") (pintype "bidirectional"))
    )
    (net (code "93") (name "unconnected-(U4B-IO-Pad98)") (class "Default")
      (node (ref "U4") (pin "98") (pinfunction "IO_98") (pintype "bidirectional"))
    )
    (net (code "94") (name "unconnected-(U4B-IO-Pad100)") (class "Default")
      (node (ref "U4") (pin "100") (pinfunction "IO_100") (pintype "bidirectional"))
    )
    (net (code "95") (name "unconnected-(U4B-IOGCLK2-Pad62)") (class "Default")
      (node (ref "U4") (pin "62") (pinfunction "IOGCLK2_62") (pintype "bidirectional"))
    )
    (net (code "96") (name "unconnected-(U4B-IOGCLK3-Pad64)") (class "Default")
      (node (ref "U4") (pin "64") (pinfunction "IOGCLK3_64") (pintype "bidirectional"))
    )
    (net (code "97") (name "unconnected-(U4E-IO-Pad2)") (class "Default")
      (node (ref "U4") (pin "2") (pinfunction "IO_2") (pintype "bidirectional"))
    )
    (net (code "98") (name "unconnected-(U4E-IO-Pad3)") (class "Default")
      (node (ref "U4") (pin "3") (pinfunction "IO_3") (pintype "bidirectional"))
    )
    (net (code "99") (name "unconnected-(U4E-IO-Pad4)") (class "Default")
      (node (ref "U4") (pin "4") (pinfunction "IO_4") (pintype "bidirectional"))
    )
    (net (code "100") (name "unconnected-(U4E-IO-Pad5)") (class "Default")
      (node (ref "U4") (pin "5") (pinfunction "IO_5") (pintype "bidirectional"))
    )
    (net (code "101") (name "unconnected-(U4E-IO-Pad6)") (class "Default")
      (node (ref "U4") (pin "6") (pinfunction "IO_6") (pintype "bidirectional"))
    )
    (net (code "102") (name "unconnected-(U4E-IO-Pad7)") (class "Default")
      (node (ref "U4") (pin "7") (pinfunction "IO_7") (pintype "bidirectional"))
    )
    (net (code "103") (name "unconnected-(U4E-IO-Pad8)") (class "Default")
      (node (ref "U4") (pin "8") (pinfunction "IO_8") (pintype "bidirectional"))
    )
    (net (code "104") (name "unconnected-(U4E-IO-Pad15)") (class "Default")
      (node (ref "U4") (pin "15") (pinfunction "IO_15") (pintype "bidirectional"))
    )
    (net (code "105") (name "unconnected-(U4E-IO-Pad16)") (class "Default")
      (node (ref "U4") (pin "16") (pinfunction "IO_16") (pintype "bidirectional"))
    )
    (net (code "106") (name "unconnected-(U4E-IO-Pad17)") (class "Default")
      (node (ref "U4") (pin "17") (pinfunction "IO_17") (pintype "bidirectional"))
    )
    (net (code "107") (name "unconnected-(U4E-IO-Pad18)") (class "Default")
      (node (ref "U4") (pin "18") (pinfunction "IO_18") (pintype "bidirectional"))
    )
    (net (code "108") (name "unconnected-(U4E-IO-Pad19)") (class "Default")
      (node (ref "U4") (pin "19") (pinfunction "IO_19") (pintype "bidirectional"))
    )
    (net (code "109") (name "unconnected-(U4E-IO-Pad20)") (class "Default")
      (node (ref "U4") (pin "20") (pinfunction "IO_20") (pintype "bidirectional"))
    )
    (net (code "110") (name "unconnected-(U4E-IO-Pad21)") (class "Default")
      (node (ref "U4") (pin "21") (pinfunction "IO_21") (pintype "bidirectional"))
    )
    (net (code "111") (name "unconnected-(U4E-IO-Pad26)") (class "Default")
      (node (ref "U4") (pin "26") (pinfunction "IO_26") (pintype "bidirectional"))
    )
    (net (code "112") (name "unconnected-(U4E-IO-Pad27)") (class "Default")
      (node (ref "U4") (pin "27") (pinfunction "IO_27") (pintype "bidirectional"))
    )
    (net (code "113") (name "unconnected-(U4E-IO-Pad28)") (class "Default")
      (node (ref "U4") (pin "28") (pinfunction "IO_28") (pintype "bidirectional"))
    )
    (net (code "114") (name "unconnected-(U4E-IO-Pad29)") (class "Default")
      (node (ref "U4") (pin "29") (pinfunction "IO_29") (pintype "bidirectional"))
    )
    (net (code "115") (name "unconnected-(U4E-IO-Pad30)") (class "Default")
      (node (ref "U4") (pin "30") (pinfunction "IO_30") (pintype "bidirectional"))
    )
    (net (code "116") (name "unconnected-(U4E-IO-Pad33)") (class "Default")
      (node (ref "U4") (pin "33") (pinfunction "IO_33") (pintype "bidirectional"))
    )
    (net (code "117") (name "unconnected-(U4E-IODEV_CLRn-Pad44)") (class "Default")
      (node (ref "U4") (pin "44") (pinfunction "IODEV_CLRn_44") (pintype "bidirectional"))
    )
    (net (code "118") (name "unconnected-(U4E-IODEV_OE-Pad43)") (class "Default")
      (node (ref "U4") (pin "43") (pinfunction "IODEV_OE_43") (pintype "bidirectional"))
    )
    (net (code "119") (name "unconnected-(U4E-IOGCLK0-Pad12)") (class "Default")
      (node (ref "U4") (pin "12") (pinfunction "IOGCLK0_12") (pintype "bidirectional"))
    )
    (net (code "120") (name "unconnected-(U4E-IOGCLK1-Pad14)") (class "Default")
      (node (ref "U4") (pin "14") (pinfunction "IOGCLK1_14") (pintype "bidirectional"))
    )
    (net (code "121") (name "unconnected-(U5-DQ8-Pad36)") (class "Default")
      (node (ref "U5") (pin "36") (pinfunction "DQ8_36") (pintype "unspecified"))
    )
    (net (code "122") (name "unconnected-(U5-DQ9-Pad38)") (class "Default")
      (node (ref "U5") (pin "38") (pinfunction "DQ9_38") (pintype "unspecified"))
    )
    (net (code "123") (name "unconnected-(U5-DQ10-Pad40)") (class "Default")
      (node (ref "U5") (pin "40") (pinfunction "DQ10_40") (pintype "unspecified"))
    )
    (net (code "124") (name "unconnected-(U5-DQ11-Pad42)") (class "Default")
      (node (ref "U5") (pin "42") (pinfunction "DQ11_42") (pintype "unspecified"))
    )
    (net (code "125") (name "unconnected-(U5-DQ12-Pad45)") (class "Default")
      (node (ref "U5") (pin "45") (pinfunction "DQ12_45") (pintype "unspecified"))
    )
    (net (code "126") (name "unconnected-(U5-DQ13-Pad47)") (class "Default")
      (node (ref "U5") (pin "47") (pinfunction "DQ13_47") (pintype "unspecified"))
    )
    (net (code "127") (name "unconnected-(U5-DQ14-Pad49)") (class "Default")
      (node (ref "U5") (pin "49") (pinfunction "DQ14_49") (pintype "unspecified"))
    )
    (net (code "128") (name "unconnected-(U5-NC-Pad27)") (class "Default")
      (node (ref "U5") (pin "27") (pinfunction "NC_27") (pintype "unspecified"))
    )
    (net (code "129") (name "unconnected-(U5-NC-Pad28)") (class "Default")
      (node (ref "U5") (pin "28") (pinfunction "NC_28") (pintype "unspecified"))
    )
    (net (code "130") (name "unconnected-(U5-NC-Pad30)") (class "Default")
      (node (ref "U5") (pin "30") (pinfunction "NC_30") (pintype "unspecified"))
    )
    (net (code "131") (name "unconnected-(U5-NC-Pad55)") (class "Default")
      (node (ref "U5") (pin "55") (pinfunction "NC_55") (pintype "unspecified"))
    )
    (net (code "132") (name "unconnected-(U5-NC-Pad56)") (class "Default")
      (node (ref "U5") (pin "56") (pinfunction "NC_56") (pintype "unspecified"))
    )
    (net (code "133") (name "unconnected-(U5-RY{slash}BY#-Pad17)") (class "Default")
      (node (ref "U5") (pin "17") (pinfunction "RY/BY#_17") (pintype "unspecified"))
    )
    (net (code "134") (name "unconnected-(U5-WP#{slash}ACC-Pad16)") (class "Default")
      (node (ref "U5") (pin "16") (pinfunction "WP#/ACC_16") (pintype "unspecified"))
    )
  )
)
